# 04_ALTIMETER.net
KiCad netlist of a schematic drawn in Altium Designer
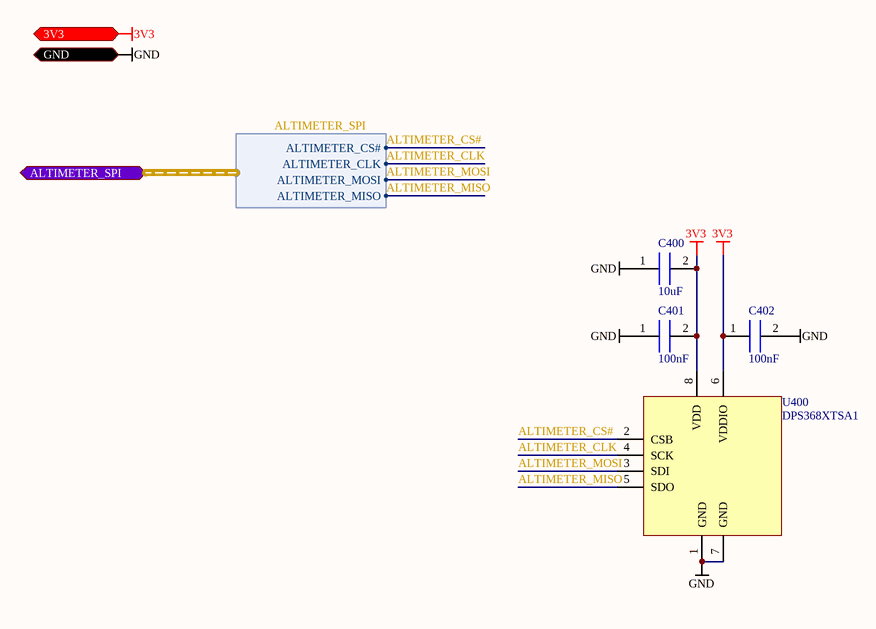
[diagram p0: 04_ALTIMETER.SchDoc]

(export (version "E")
  (design (tool "Eeschema 10.0.6"))
  (components
    (comp (ref "C400")
      (value "10uF")
      (footprint "CAP_0402")
      (description "CAPACITOR 10uF 20% 6.3V 0402 GRM155R60J106ME05D")
      (fields (field (name "TOLERANCE") "20%") (field (name "MANUFACTURER") "MURATA"))
      (libsource (lib "Capacitors") (part "10uF 20% 6.3V 0402 GRM155R60J106ME05D"))
    )
    (comp (ref "C401")
      (value "100nF")
      (footprint "CAP_0402")
      (description "CAPACITOR 100nF 10% X7R 0402")
      (fields (field (name "TOLERANCE") "10%") (field (name "MANUFACTURER") "MURATA"))
      (libsource (lib "Capacitors") (part "100nF_10%_16V_0402_GRM155R71C104KA88J"))
    )
    (comp (ref "C402")
      (value "100nF")
      (footprint "CAP_0402")
      (description "CAPACITOR 100nF 10% X7R 0402")
      (fields (field (name "TOLERANCE") "10%") (field (name "MANUFACTURER") "MURATA"))
      (libsource (lib "Capacitors") (part "100nF_10%_16V_0402_GRM155R71C104KA88J"))
    )
    (comp (ref "U400")
      (value "BAR_4V_0.002hPA_500nA_DPS368XTSA1")
      (description "BAROMETRIC SENSOR 4V 0.002hPA 500nA DPS368XTSA1")
      (fields (field (name "MANUFACTURER") "INFINEON") (field (name "MANUFACTURER REFERENCE") "DPS368XTSA1"))
      (libsource (lib "Semiconductor") (part "BAR_4V_0.002hPA_500nA_DPS368XTSA1"))
    )
  )
  (nets
    (net (code "2") (name "/ALTIMETER_CLK") (class "Default")
      (node (ref "U400") (pin "4") (pinfunction "SCK_4") (pintype "passive"))
    )
    (net (code "3") (name "/ALTIMETER_CS#") (class "Default")
      (node (ref "U400") (pin "2") (pinfunction "CSB_2") (pintype "passive"))
    )
    (net (code "4") (name "/ALTIMETER_MISO") (class "Default")
      (node (ref "U400") (pin "5") (pinfunction "SDO_5") (pintype "passive"))
    )
    (net (code "5") (name "/ALTIMETER_MOSI") (class "Default")
      (node (ref "U400") (pin "3") (pinfunction "SDI_3") (pintype "passive"))
    )
    (net (code "7") (name "3V3") (class "Default")
      (node (ref "C400") (pin "2") (pinfunction "2_2") (pintype "passive"))
      (node (ref "C401") (pin "2") (pinfunction "2_2") (pintype "passive"))
      (node (ref "C402") (pin "1") (pinfunction "1_1") (pintype "passive"))
      (node (ref "U400") (pin "6") (pinfunction "VDDIO_6") (pintype "passive"))
      (node (ref "U400") (pin "8") (pinfunction "VDD_8") (pintype "passive"))
    )
    (net (code "8") (name "GND") (class "Default")
      (node (ref "C400") (pin "1") (pinfunction "1_1") (pintype "passive"))
      (node (ref "C401") (pin "1") (pinfunction "1_1") (pintype "passive"))
      (node (ref "C402") (pin "2") (pinfunction "2_2") (pintype "passive"))
      (node (ref "U400") (pin "1") (pinfunction "GND_1") (pintype "passive"))
      (node (ref "U400") (pin "7") (pinfunction "GND_7") (pintype "passive"))
    )
  )
)
